# 1_Controller.net
KiCad netlist of a schematic drawn in Altium Designer
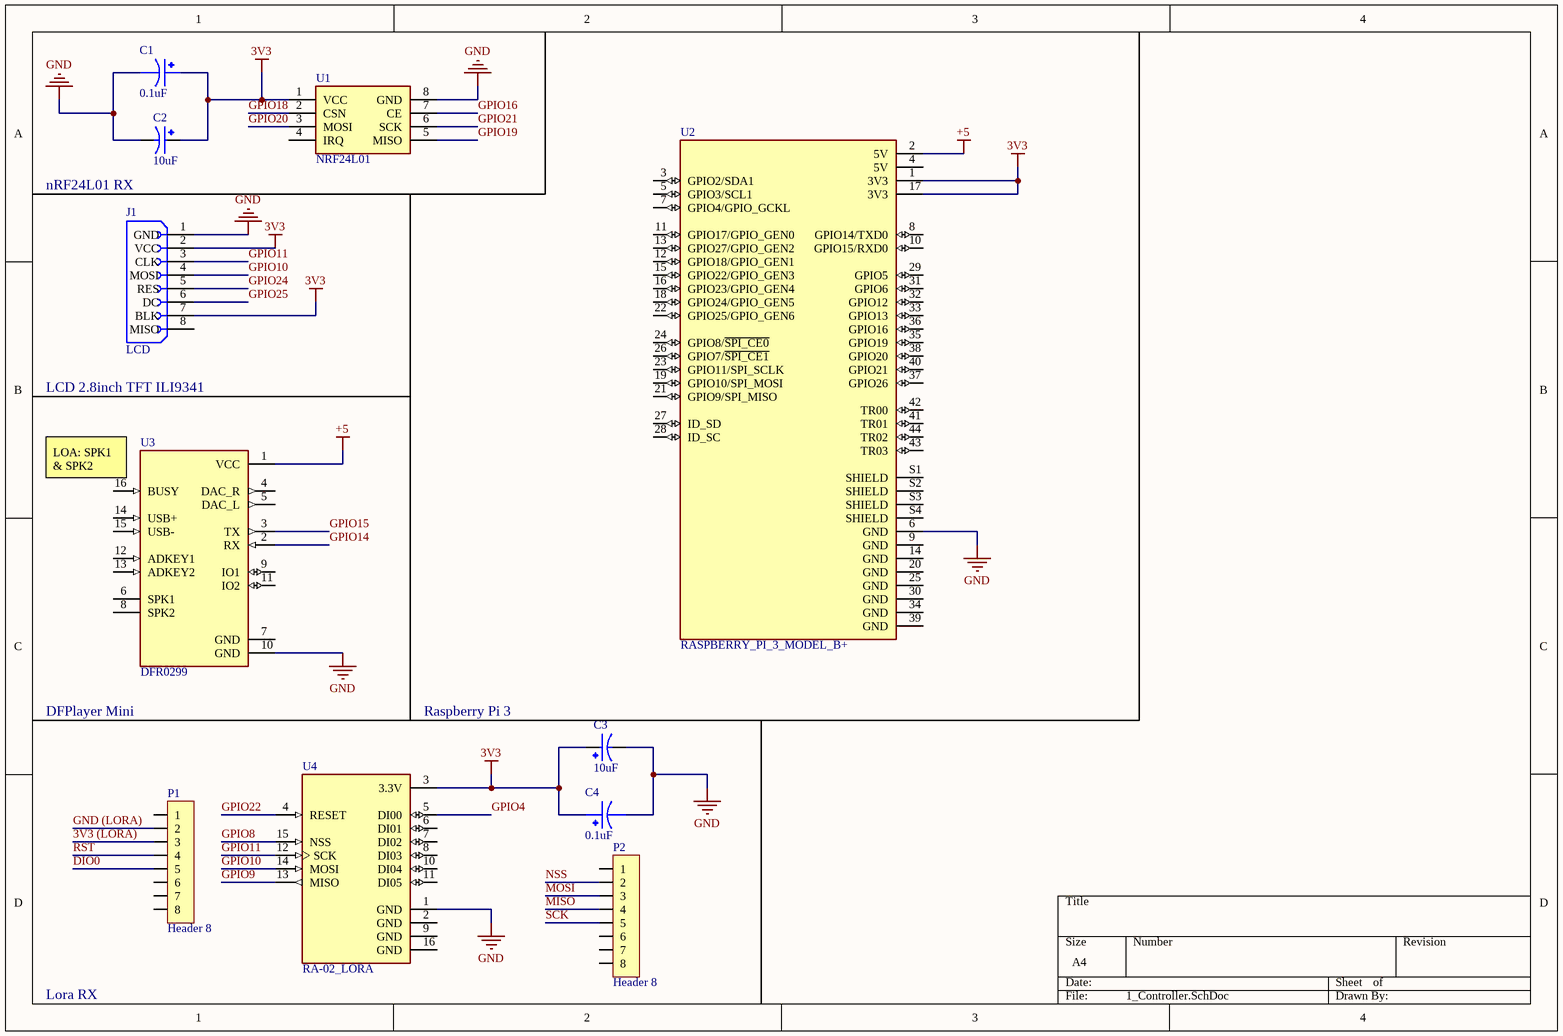
[diagram p0: 1_Controller.SchDoc]

(export (version "E")
  (design (tool "Eeschema 10.0.6"))
  (components
    (comp (ref "C1")
      (value "0.1uF")
      (footprint "CAPPRD200W50D550H1250")
      (description "0.1 ÂµF 100 V Aluminum Electrolytic Capacitors Radial, Can - 2000 Hrs @ 85Â°C")
      (fields (field (name "MF") "Nichicon") (field (name "MP") "UVR2A0R1MDD"))
      (libsource (lib "") (part "UVR2A0R1MDD_1"))
    )
    (comp (ref "C2")
      (value "10uF")
      (footprint "CAPPRD500W50D500H1100")
      (description "10ÂµF 63V Aluminum Electrolytic Capacitors Radial, Can 2000 Hrs @ 85Â°C")
      (fields (field (name "MF") "Panasonic") (field (name "MP") "ECA1JM100B"))
      (libsource (lib "ECA1JM100B") (part "ECA1JM100B"))
    )
    (comp (ref "C3")
      (value "10uF")
      (footprint "CAPPRD500W50D500H1100")
      (description "10ÂµF 63V Aluminum Electrolytic Capacitors Radial, Can 2000 Hrs @ 85Â°C")
      (fields (field (name "MF") "Panasonic") (field (name "MP") "ECA1JM100B"))
      (libsource (lib "") (part "ECA1JM100B_1"))
    )
    (comp (ref "C4")
      (value "0.1uF")
      (footprint "CAPPRD200W50D550H1250")
      (description "0.1 ÂµF 100 V Aluminum Electrolytic Capacitors Radial, Can - 2000 Hrs @ 85Â°C")
      (fields (field (name "MF") "Nichicon") (field (name "MP") "UVR2A0R1MDD"))
      (libsource (lib "UVR2A0R1MDD") (part "UVR2A0R1MDD"))
    )
    (comp (ref "J1")
      (value "LCD")
      (footprint "GRAVITECH_8FX1-254MM")
      (description "Headers & Wire Housings 2.54MM 0.1 8-PIN FEMALE HEADER")
      (fields (field (name "MP") "8Fx1-254mm") (field (name "MF") "Gravitech"))
      (libsource (lib "8FX1-254MM") (part "8FX1-254MM"))
    )
    (comp (ref "P1")
      (value "Header 8")
      (footprint "HDR/Header/8")
      (description "Header, 8-Pin")
      (libsource (lib "connectors") (part "Header 8"))
    )
    (comp (ref "P2")
      (value "Header 8")
      (footprint "HDR/Header/8")
      (description "Header, 8-Pin")
      (libsource (lib "connectors") (part "Header 8"))
    )
    (comp (ref "U1")
      (value "NRF24L01")
      (footprint "NRF24L01")
      (description "MÓDULO TRANSCEPTOR RF WIRELESS 2.4GHZ")
      (libsource (lib "Communication") (part "NRF24L01"))
    )
    (comp (ref "U2")
      (value "RASPBERRY_PI_3_MODEL_B+")
      (footprint "MODULE_RASPBERRY_PI_3_MODEL_B+")
      (fields (field (name "MF") "Raspberry Pi") (field (name "MP") "RASPBERRY PI 3 MODEL B+"))
      (libsource (lib "RASPBERRY_PI_3_MODEL_B_") (part "RASPBERRY_PI_3_MODEL_B+"))
    )
    (comp (ref "U3")
      (value "DFR0299")
      (footprint "MODULE_DFR0299")
      (description "- MP3 Player Audio Arduino Platform Evaluation Expansion Board")
      (fields (field (name "MF") "DFRobot"))
      (libsource (lib "DFR0299") (part "DFR0299"))
    )
    (comp (ref "U4")
      (value "RA-02_LORA")
      (footprint "MODULE_RA-02_LORA")
      (description "Ra-02 LoRa RF M5Stack Platform Evaluation Expansion Board")
      (libsource (lib "RA-02_LORA") (part "RA-02_LORA"))
    )
  )
  (nets
    (net (code "1") (name "+5") (class "Default")
      (node (ref "U2") (pin "2") (pinfunction "5V_2") (pintype "power_in"))
      (node (ref "U3") (pin "1") (pinfunction "VCC_1") (pintype "power_in"))
    )
    (net (code "2") (name "/3V3 (LORA)") (class "Default")
      (node (ref "P1") (pin "3") (pinfunction "3_3") (pintype "passive"))
    )
    (net (code "3") (name "/DIO0") (class "Default")
      (node (ref "P1") (pin "5") (pinfunction "5_5") (pintype "passive"))
    )
    (net (code "4") (name "/GND (LORA)") (class "Default")
      (node (ref "P1") (pin "2") (pinfunction "2_2") (pintype "passive"))
    )
    (net (code "5") (name "/GPIO4") (class "Default")
      (node (ref "U4") (pin "5") (pinfunction "DI00_5") (pintype "bidirectional"))
    )
    (net (code "6") (name "/GPIO8") (class "Default")
      (node (ref "U4") (pin "15") (pinfunction "NSS_15") (pintype "input"))
    )
    (net (code "7") (name "/GPIO9") (class "Default")
      (node (ref "U4") (pin "13") (pinfunction "MISO_13") (pintype "output"))
    )
    (net (code "8") (name "/GPIO10") (class "Default")
      (node (ref "J1") (pin "4") (pinfunction "MOSI_4") (pintype "passive"))
      (node (ref "U4") (pin "14") (pinfunction "MOSI_14") (pintype "input"))
    )
    (net (code "9") (name "/GPIO11") (class "Default")
      (node (ref "J1") (pin "3") (pinfunction "CLK_3") (pintype "passive"))
      (node (ref "U4") (pin "12") (pinfunction "SCK_12") (pintype "input"))
    )
    (net (code "10") (name "/GPIO14") (class "Default")
      (node (ref "U3") (pin "2") (pinfunction "RX_2") (pintype "input"))
    )
    (net (code "11") (name "/GPIO15") (class "Default")
      (node (ref "U3") (pin "3") (pinfunction "TX_3") (pintype "output"))
    )
    (net (code "12") (name "/GPIO16") (class "Default")
      (node (ref "U1") (pin "7") (pinfunction "CE_7") (pintype "passive"))
    )
    (net (code "13") (name "/GPIO18") (class "Default")
      (node (ref "U1") (pin "2") (pinfunction "CSN_2") (pintype "passive"))
    )
    (net (code "14") (name "/GPIO19") (class "Default")
      (node (ref "U1") (pin "5") (pinfunction "MISO_5") (pintype "passive"))
    )
    (net (code "15") (name "/GPIO20") (class "Default")
      (node (ref "U1") (pin "3") (pinfunction "MOSI_3") (pintype "passive"))
    )
    (net (code "16") (name "/GPIO21") (class "Default")
      (node (ref "U1") (pin "6") (pinfunction "SCK_6") (pintype "passive"))
    )
    (net (code "17") (name "/GPIO22") (class "Default")
      (node (ref "U4") (pin "4") (pinfunction "RESET_4") (pintype "input"))
    )
    (net (code "18") (name "/GPIO24") (class "Default")
      (node (ref "J1") (pin "5") (pinfunction "RES_5") (pintype "passive"))
    )
    (net (code "19") (name "/GPIO25") (class "Default")
      (node (ref "J1") (pin "6") (pinfunction "DC_6") (pintype "passive"))
    )
    (net (code "20") (name "/MISO") (class "Default")
      (node (ref "P2") (pin "4") (pinfunction "4_4") (pintype "passive"))
    )
    (net (code "21") (name "/MOSI") (class "Default")
      (node (ref "P2") (pin "3") (pinfunction "3_3") (pintype "passive"))
    )
    (net (code "22") (name "/NSS") (class "Default")
      (node (ref "P2") (pin "2") (pinfunction "2_2") (pintype "passive"))
    )
    (net (code "23") (name "/RST") (class "Default")
      (node (ref "P1") (pin "4") (pinfunction "4_4") (pintype "passive"))
    )
    (net (code "24") (name "/SCK") (class "Default")
      (node (ref "P2") (pin "5") (pinfunction "5_5") (pintype "passive"))
    )
    (net (code "25") (name "3V3") (class "Default")
      (node (ref "C1") (pin "1") (pinfunction "1_1") (pintype "passive"))
      (node (ref "C2") (pin "P") (pinfunction "P_P") (pintype "passive"))
      (node (ref "C3") (pin "P") (pinfunction "P_P") (pintype "passive"))
      (node (ref "C4") (pin "1") (pinfunction "1_1") (pintype "passive"))
      (node (ref "J1") (pin "2") (pinfunction "VCC_2") (pintype "passive"))
      (node (ref "J1") (pin "7") (pinfunction "BLK_7") (pintype "passive"))
      (node (ref "U1") (pin "1") (pinfunction "VCC_1") (pintype "passive"))
      (node (ref "U2") (pin "1") (pinfunction "3V3_1") (pintype "power_in"))
      (node (ref "U2") (pin "17") (pinfunction "3V3_17") (pintype "power_in"))
      (node (ref "U4") (pin "3") (pinfunction "3.3V_3") (pintype "power_in"))
    )
    (net (code "26") (name "GND") (class "Default")
      (node (ref "C1") (pin "2") (pinfunction "2_2") (pintype "passive"))
      (node (ref "C2") (pin "N") (pinfunction "N_N") (pintype "passive"))
      (node (ref "C3") (pin "N") (pinfunction "N_N") (pintype "passive"))
      (node (ref "C4") (pin "2") (pinfunction "2_2") (pintype "passive"))
      (node (ref "J1") (pin "1") (pinfunction "GND_1") (pintype "passive"))
      (node (ref "U1") (pin "8") (pinfunction "GND_8") (pintype "passive"))
      (node (ref "U2") (pin "6") (pinfunction "GND_6") (pintype "power_in"))
      (node (ref "U3") (pin "10") (pinfunction "GND_10") (pintype "power_in"))
      (node (ref "U4") (pin "1") (pinfunction "GND_1") (pintype "power_in"))
    )
    (net (code "27") (name "unconnected-(J1-MISO-Pad8)") (class "Default")
      (node (ref "J1") (pin "8") (pinfunction "MISO_8") (pintype "passive"))
    )
    (net (code "28") (name "unconnected-(P1-Pad1)") (class "Default")
      (node (ref "P1") (pin "1") (pinfunction "1_1") (pintype "passive"))
    )
    (net (code "29") (name "unconnected-(P1-Pad6)") (class "Default")
      (node (ref "P1") (pin "6") (pinfunction "6_6") (pintype "passive"))
    )
    (net (code "30") (name "unconnected-(P1-Pad7)") (class "Default")
      (node (ref "P1") (pin "7") (pinfunction "7_7") (pintype "passive"))
    )
    (net (code "31") (name "unconnected-(P1-Pad8)") (class "Default")
      (node (ref "P1") (pin "8") (pinfunction "8_8") (pintype "passive"))
    )
    (net (code "32") (name "unconnected-(P2-Pad1)") (class "Default")
      (node (ref "P2") (pin "1") (pinfunction "1_1") (pintype "passive"))
    )
    (net (code "33") (name "unconnected-(P2-Pad6)") (class "Default")
      (node (ref "P2") (pin "6") (pinfunction "6_6") (pintype "passive"))
    )
    (net (code "34") (name "unconnected-(P2-Pad7)") (class "Default")
      (node (ref "P2") (pin "7") (pinfunction "7_7") (pintype "passive"))
    )
    (net (code "35") (name "unconnected-(P2-Pad8)") (class "Default")
      (node (ref "P2") (pin "8") (pinfunction "8_8") (pintype "passive"))
    )
    (net (code "36") (name "unconnected-(U1-IRQ-Pad4)") (class "Default")
      (node (ref "U1") (pin "4") (pinfunction "IRQ_4") (pintype "passive"))
    )
    (net (code "37") (name "unconnected-(U2-5V-Pad4)") (class "Default")
      (node (ref "U2") (pin "4") (pinfunction "5V_4") (pintype "power_in"))
    )
    (net (code "38") (name "unconnected-(U2-GND-Pad9)") (class "Default")
      (node (ref "U2") (pin "9") (pinfunction "GND_9") (pintype "power_in"))
    )
    (net (code "39") (name "unconnected-(U2-GND-Pad14)") (class "Default")
      (node (ref "U2") (pin "14") (pinfunction "GND_14") (pintype "power_in"))
    )
    (net (code "40") (name "unconnected-(U2-GND-Pad20)") (class "Default")
      (node (ref "U2") (pin "20") (pinfunction "GND_20") (pintype "power_in"))
    )
    (net (code "41") (name "unconnected-(U2-GND-Pad25)") (class "Default")
      (node (ref "U2") (pin "25") (pinfunction "GND_25") (pintype "power_in"))
    )
    (net (code "42") (name "unconnected-(U2-GND-Pad30)") (class "Default")
      (node (ref "U2") (pin "30") (pinfunction "GND_30") (pintype "power_in"))
    )
    (net (code "43") (name "unconnected-(U2-GND-Pad34)") (class "Default")
      (node (ref "U2") (pin "34") (pinfunction "GND_34") (pintype "power_in"))
    )
    (net (code "44") (name "unconnected-(U2-GND-Pad39)") (class "Default")
      (node (ref "U2") (pin "39") (pinfunction "GND_39") (pintype "power_in"))
    )
    (net (code "45") (name "unconnected-(U2-GPIO2{slash}SDA1-Pad3)") (class "Default")
      (node (ref "U2") (pin "3") (pinfunction "GPIO2/SDA1_3") (pintype "bidirectional"))
    )
    (net (code "46") (name "unconnected-(U2-GPIO3{slash}SCL1-Pad5)") (class "Default")
      (node (ref "U2") (pin "5") (pinfunction "GPIO3/SCL1_5") (pintype "bidirectional"))
    )
    (net (code "47") (name "unconnected-(U2-GPIO4{slash}GPIO_GCKL-Pad7)") (class "Default")
      (node (ref "U2") (pin "7") (pinfunction "GPIO4/GPIO_GCKL_7") (pintype "bidirectional"))
    )
    (net (code "48") (name "unconnected-(U2-GPIO5-Pad29)") (class "Default")
      (node (ref "U2") (pin "29") (pinfunction "GPIO5_29") (pintype "bidirectional"))
    )
    (net (code "49") (name "unconnected-(U2-GPIO6-Pad31)") (class "Default")
      (node (ref "U2") (pin "31") (pinfunction "GPIO6_31") (pintype "bidirectional"))
    )
    (net (code "50") (name "unconnected-(U2-GPIO7{slash}~{SPI_CE1}-Pad26)") (class "Default")
      (node (ref "U2") (pin "26") (pinfunction "GPIO7/~{SPI_CE1}_26") (pintype "bidirectional"))
    )
    (net (code "51") (name "unconnected-(U2-GPIO8{slash}~{SPI_CE0}-Pad24)") (class "Default")
      (node (ref "U2") (pin "24") (pinfunction "GPIO8/~{SPI_CE0}_24") (pintype "bidirectional"))
    )
    (net (code "52") (name "unconnected-(U2-GPIO9{slash}SPI_MISO-Pad21)") (class "Default")
      (node (ref "U2") (pin "21") (pinfunction "GPIO9/SPI_MISO_21") (pintype "bidirectional"))
    )
    (net (code "53") (name "unconnected-(U2-GPIO10{slash}SPI_MOSI-Pad19)") (class "Default")
      (node (ref "U2") (pin "19") (pinfunction "GPIO10/SPI_MOSI_19") (pintype "bidirectional"))
    )
    (net (code "54") (name "unconnected-(U2-GPIO11{slash}SPI_SCLK-Pad23)") (class "Default")
      (node (ref "U2") (pin "23") (pinfunction "GPIO11/SPI_SCLK_23") (pintype "bidirectional"))
    )
    (net (code "55") (name "unconnected-(U2-GPIO12-Pad32)") (class "Default")
      (node (ref "U2") (pin "32") (pinfunction "GPIO12_32") (pintype "bidirectional"))
    )
    (net (code "56") (name "unconnected-(U2-GPIO13-Pad33)") (class "Default")
      (node (ref "U2") (pin "33") (pinfunction "GPIO13_33") (pintype "bidirectional"))
    )
    (net (code "57") (name "unconnected-(U2-GPIO14{slash}TXD0-Pad8)") (class "Default")
      (node (ref "U2") (pin "8") (pinfunction "GPIO14/TXD0_8") (pintype "bidirectional"))
    )
    (net (code "58") (name "unconnected-(U2-GPIO15{slash}RXD0-Pad10)") (class "Default")
      (node (ref "U2") (pin "10") (pinfunction "GPIO15/RXD0_10") (pintype "bidirectional"))
    )
    (net (code "59") (name "unconnected-(U2-GPIO16-Pad36)") (class "Default")
      (node (ref "U2") (pin "36") (pinfunction "GPIO16_36") (pintype "bidirectional"))
    )
    (net (code "60") (name "unconnected-(U2-GPIO17{slash}GPIO_GEN0-Pad11)") (class "Default")
      (node (ref "U2") (pin "11") (pinfunction "GPIO17/GPIO_GEN0_11") (pintype "bidirectional"))
    )
    (net (code "61") (name "unconnected-(U2-GPIO18{slash}GPIO_GEN1-Pad12)") (class "Default")
      (node (ref "U2") (pin "12") (pinfunction "GPIO18/GPIO_GEN1_12") (pintype "bidirectional"))
    )
    (net (code "62") (name "unconnected-(U2-GPIO19-Pad35)") (class "Default")
      (node (ref "U2") (pin "35") (pinfunction "GPIO19_35") (pintype "bidirectional"))
    )
    (net (code "63") (name "unconnected-(U2-GPIO20-Pad38)") (class "Default")
      (node (ref "U2") (pin "38") (pinfunction "GPIO20_38") (pintype "bidirectional"))
    )
    (net (code "64") (name "unconnected-(U2-GPIO21-Pad40)") (class "Default")
      (node (ref "U2") (pin "40") (pinfunction "GPIO21_40") (pintype "bidirectional"))
    )
    (net (code "65") (name "unconnected-(U2-GPIO22{slash}GPIO_GEN3-Pad15)") (class "Default")
      (node (ref "U2") (pin "15") (pinfunction "GPIO22/GPIO_GEN3_15") (pintype "bidirectional"))
    )
    (net (code "66") (name "unconnected-(U2-GPIO23{slash}GPIO_GEN4-Pad16)") (class "Default")
      (node (ref "U2") (pin "16") (pinfunction "GPIO23/GPIO_GEN4_16") (pintype "bidirectional"))
    )
    (net (code "67") (name "unconnected-(U2-GPIO24{slash}GPIO_GEN5-Pad18)") (class "Default")
      (node (ref "U2") (pin "18") (pinfunction "GPIO24/GPIO_GEN5_18") (pintype "bidirectional"))
    )
    (net (code "68") (name "unconnected-(U2-GPIO25{slash}GPIO_GEN6-Pad22)") (class "Default")
      (node (ref "U2") (pin "22") (pinfunction "GPIO25/GPIO_GEN6_22") (pintype "bidirectional"))
    )
    (net (code "69") (name "unconnected-(U2-GPIO26-Pad37)") (class "Default")
      (node (ref "U2") (pin "37") (pinfunction "GPIO26_37") (pintype "bidirectional"))
    )
    (net (code "70") (name "unconnected-(U2-GPIO27{slash}GPIO_GEN2-Pad13)") (class "Default")
      (node (ref "U2") (pin "13") (pinfunction "GPIO27/GPIO_GEN2_13") (pintype "bidirectional"))
    )
    (net (code "71") (name "unconnected-(U2-ID_SC-Pad28)") (class "Default")
      (node (ref "U2") (pin "28") (pinfunction "ID_SC_28") (pintype "bidirectional"))
    )
    (net (code "72") (name "unconnected-(U2-ID_SD-Pad27)") (class "Default")
      (node (ref "U2") (pin "27") (pinfunction "ID_SD_27") (pintype "bidirectional"))
    )
    (net (code "73") (name "unconnected-(U2-SHIELD-PadS1)") (class "Default")
      (node (ref "U2") (pin "S1") (pinfunction "SHIELD_S1") (pintype "power_in"))
    )
    (net (code "74") (name "unconnected-(U2-SHIELD-PadS2)") (class "Default")
      (node (ref "U2") (pin "S2") (pinfunction "SHIELD_S2") (pintype "power_in"))
    )
    (net (code "75") (name "unconnected-(U2-SHIELD-PadS3)") (class "Default")
      (node (ref "U2") (pin "S3") (pinfunction "SHIELD_S3") (pintype "power_in"))
    )
    (net (code "76") (name "unconnected-(U2-SHIELD-PadS4)") (class "Default")
      (node (ref "U2") (pin "S4") (pinfunction "SHIELD_S4") (pintype "power_in"))
    )
    (net (code "77") (name "unconnected-(U2-TR00-Pad42)") (class "Default")
      (node (ref "U2") (pin "42") (pinfunction "TR00_42") (pintype "bidirectional"))
    )
    (net (code "78") (name "unconnected-(U2-TR01-Pad41)") (class "Default")
      (node (ref "U2") (pin "41") (pinfunction "TR01_41") (pintype "bidirectional"))
    )
    (net (code "79") (name "unconnected-(U2-TR02-Pad44)") (class "Default")
      (node (ref "U2") (pin "44") (pinfunction "TR02_44") (pintype "bidirectional"))
    )
    (net (code "80") (name "unconnected-(U2-TR03-Pad43)") (class "Default")
      (node (ref "U2") (pin "43") (pinfunction "TR03_43") (pintype "bidirectional"))
    )
    (net (code "81") (name "unconnected-(U3-ADKEY1-Pad12)") (class "Default")
      (node (ref "U3") (pin "12") (pinfunction "ADKEY1_12") (pintype "input"))
    )
    (net (code "82") (name "unconnected-(U3-ADKEY2-Pad13)") (class "Default")
      (node (ref "U3") (pin "13") (pinfunction "ADKEY2_13") (pintype "input"))
    )
    (net (code "83") (name "unconnected-(U3-BUSY-Pad16)") (class "Default")
      (node (ref "U3") (pin "16") (pinfunction "BUSY_16") (pintype "input"))
    )
    (net (code "84") (name "unconnected-(U3-DAC_L-Pad5)") (class "Default")
      (node (ref "U3") (pin "5") (pinfunction "DAC_L_5") (pintype "output"))
    )
    (net (code "85") (name "unconnected-(U3-DAC_R-Pad4)") (class "Default")
      (node (ref "U3") (pin "4") (pinfunction "DAC_R_4") (pintype "output"))
    )
    (net (code "86") (name "unconnected-(U3-GND-Pad7)") (class "Default")
      (node (ref "U3") (pin "7") (pinfunction "GND_7") (pintype "power_in"))
    )
    (net (code "87") (name "unconnected-(U3-IO1-Pad9)") (class "Default")
      (node (ref "U3") (pin "9") (pinfunction "IO1_9") (pintype "bidirectional"))
    )
    (net (code "88") (name "unconnected-(U3-IO2-Pad11)") (class "Default")
      (node (ref "U3") (pin "11") (pinfunction "IO2_11") (pintype "bidirectional"))
    )
    (net (code "89") (name "unconnected-(U3-SPK1-Pad6)") (class "Default")
      (node (ref "U3") (pin "6") (pinfunction "SPK1_6") (pintype "passive"))
    )
    (net (code "90") (name "unconnected-(U3-SPK2-Pad8)") (class "Default")
      (node (ref "U3") (pin "8") (pinfunction "SPK2_8") (pintype "passive"))
    )
    (net (code "91") (name "unconnected-(U3-USB+-Pad14)") (class "Default")
      (node (ref "U3") (pin "14") (pinfunction "USB+_14") (pintype "input"))
    )
    (net (code "92") (name "unconnected-(U3-USB--Pad15)") (class "Default")
      (node (ref "U3") (pin "15") (pinfunction "USB-_15") (pintype "input"))
    )
    (net (code "93") (name "unconnected-(U4-DI01-Pad6)") (class "Default")
      (node (ref "U4") (pin "6") (pinfunction "DI01_6") (pintype "bidirectional"))
    )
    (net (code "94") (name "unconnected-(U4-DI02-Pad7)") (class "Default")
      (node (ref "U4") (pin "7") (pinfunction "DI02_7") (pintype "bidirectional"))
    )
    (net (code "95") (name "unconnected-(U4-DI03-Pad8)") (class "Default")
      (node (ref "U4") (pin "8") (pinfunction "DI03_8") (pintype "bidirectional"))
    )
    (net (code "96") (name "unconnected-(U4-DI04-Pad10)") (class "Default")
      (node (ref "U4") (pin "10") (pinfunction "DI04_10") (pintype "bidirectional"))
    )
    (net (code "97") (name "unconnected-(U4-DI05-Pad11)") (class "Default")
      (node (ref "U4") (pin "11") (pinfunction "DI05_11") (pintype "bidirectional"))
    )
    (net (code "98") (name "unconnected-(U4-GND-Pad2)") (class "Default")
      (node (ref "U4") (pin "2") (pinfunction "GND_2") (pintype "power_in"))
    )
    (net (code "99") (name "unconnected-(U4-GND-Pad9)") (class "Default")
      (node (ref "U4") (pin "9") (pinfunction "GND_9") (pintype "power_in"))
    )
    (net (code "100") (name "unconnected-(U4-GND-Pad16)") (class "Default")
      (node (ref "U4") (pin "16") (pinfunction "GND_16") (pintype "power_in"))
    )
  )
)
